# LED_Module.net
KiCad netlist of a schematic drawn in Altium Designer
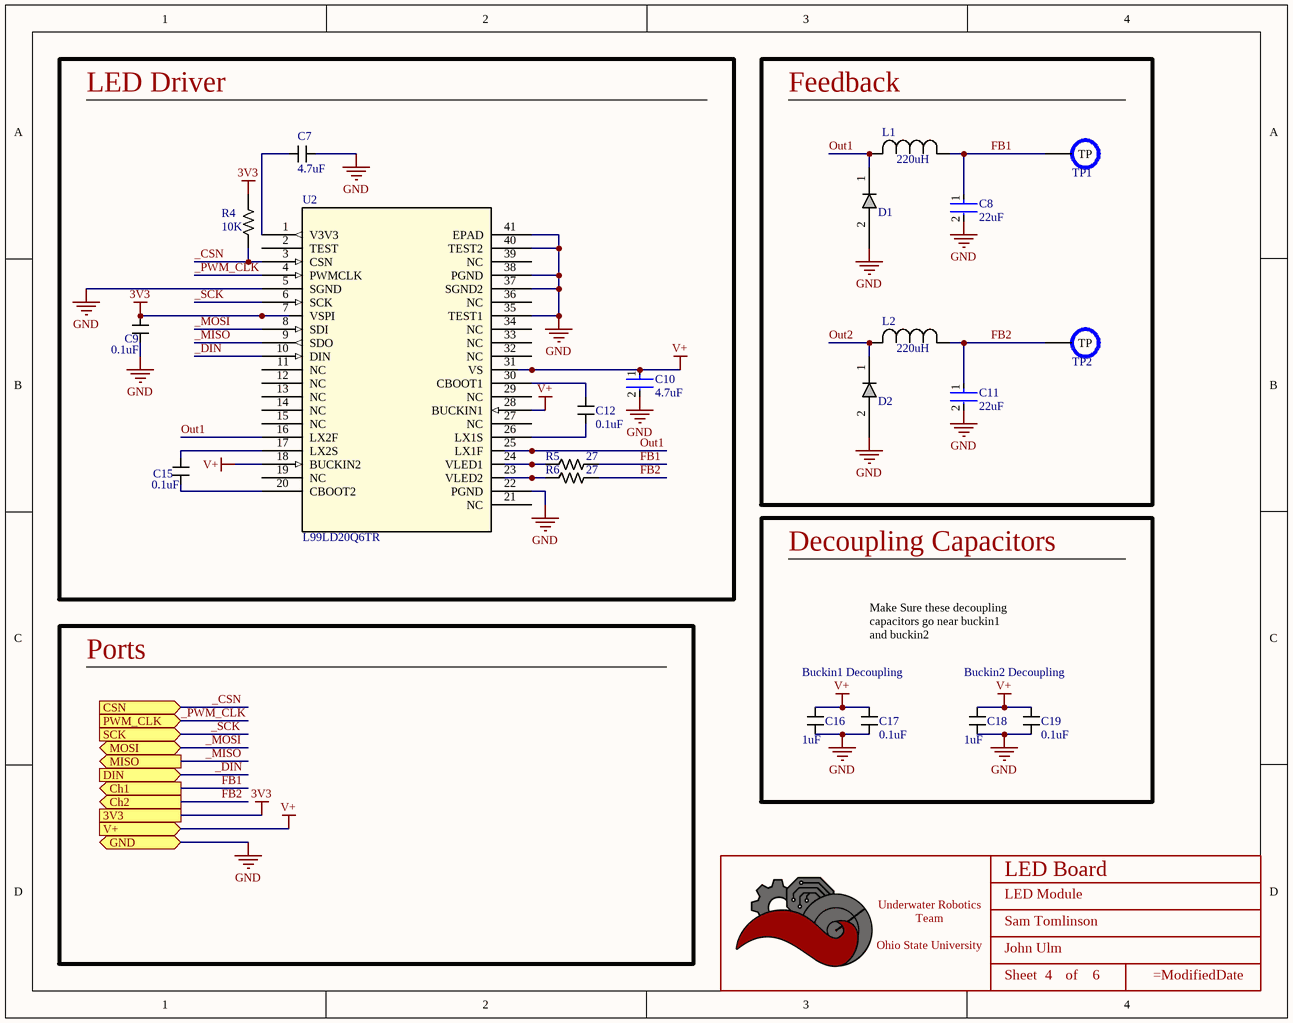
[diagram p0: LED_Module.SchDoc]

(export (version "E")
  (design (tool "Eeschema 10.0.6"))
  (components
    (comp (ref "*")
      (value "Title_Block")
      (footprint "LOGO")
      (description "UWRT Schematic Title Block Template\r\n\r\nCreated June 2021, Dylan Trainor")
      (libsource (lib "UWRT") (part "Title_Block"))
    )
    (comp (ref "C7")
      (value "4.7uF")
      (footprint "CAPACITOR_0603")
      (description "Cap 4.7uF 6.3V +/-10%\r\nCeramic 0603")
      (fields
        (field (name "TOLERANCE") "+/- 10%")
        (field (name "VOLTAGE") "6.3V")
        (field (name "MADE BY") "Robert Pafford")
      )
      (libsource (lib "Capacitors") (part "CAPACITOR_4.7uF_0603"))
    )
    (comp (ref "C8")
      (value "22uF")
      (footprint "FP-C2012-125-0_2-MFG")
      (description "Multilayer Ceramic Capacitors 22μF ±20% 35V X5R SMD 0805")
      (fields (field (name "TOLERANCE") "20%"))
      (libsource (lib "Altium Content Vault") (part "b4654b650e69147ec39a6b967a45e02"))
    )
    (comp (ref "C9")
      (value "0.1uF")
      (footprint "CAPACITOR_0603")
      (description "Cap 100nF 6.3V +/-10%\r\nCeramic 0603")
      (fields
        (field (name "TOLERANCE") "+/- 10%")
        (field (name "VOLTAGE") "6.3V")
        (field (name "MADE BY") "Flip B")
      )
      (libsource (lib "Capacitors") (part "CAPACITOR_0.1uF_0603_1"))
    )
    (comp (ref "C10")
      (value "4.7uF")
      (footprint "CAPACITOR_0603")
      (description "Chip Multilayer Ceramic Capacitors for General Purpose, 0603, 4.7uF, X5R, 15%, 20%, 35V")
      (fields (field (name "TOLERANCE") "20%"))
      (libsource (lib "Capacitors") (part "CAP CERM 4.7UF 20% 35V"))
    )
    (comp (ref "C11")
      (value "22uF")
      (footprint "FP-C2012-125-0_2-MFG")
      (description "Multilayer Ceramic Capacitors 22μF ±20% 35V X5R SMD 0805")
      (fields (field (name "TOLERANCE") "20%"))
      (libsource (lib "Altium Content Vault") (part "b4654b650e69147ec39a6b967a45e02"))
    )
    (comp (ref "C12")
      (value "0.1uF")
      (footprint "CAPACITOR_0603")
      (description "Cap 100nF 25V +/-10%\r\nCeramic 0603")
      (fields
        (field (name "TOLERANCE") "+/- 10%")
        (field (name "VOLTAGE") "6.3V")
        (field (name "MADE BY") "Flip B")
      )
      (libsource (lib "Capacitors") (part "CAPACITOR_0.1uF_0603_25V"))
    )
    (comp (ref "C15")
      (value "0.1uF")
      (footprint "CAPACITOR_0603")
      (description "Cap 100nF 25V +/-10%\r\nCeramic 0603")
      (fields
        (field (name "TOLERANCE") "+/- 10%")
        (field (name "VOLTAGE") "6.3V")
        (field (name "MADE BY") "Flip B")
      )
      (libsource (lib "Capacitors") (part "CAPACITOR_0.1uF_0603_25V"))
    )
    (comp (ref "C16")
      (value "1uF")
      (footprint "CAPACITOR_0603")
      (description "Cap 1uF 25V +/-10%\r\nCeramic 0603")
      (fields
        (field (name "TOLERANCE") "+/- 10%")
        (field (name "VOLTAGE") "16V")
        (field (name "MADE BY") "Flip B")
      )
      (libsource (lib "Capacitors") (part "CAPACITOR_1uF_0603_25V"))
    )
    (comp (ref "C17")
      (value "0.1uF")
      (footprint "CAPACITOR_0603")
      (description "Cap 100nF 25V +/-10%\r\nCeramic 0603")
      (fields
        (field (name "TOLERANCE") "+/- 10%")
        (field (name "VOLTAGE") "6.3V")
        (field (name "MADE BY") "Flip B")
      )
      (libsource (lib "Capacitors") (part "CAPACITOR_0.1uF_0603_25V"))
    )
    (comp (ref "C18")
      (value "1uF")
      (footprint "CAPACITOR_0603")
      (description "Cap 1uF 25V +/-10%\r\nCeramic 0603")
      (fields
        (field (name "TOLERANCE") "+/- 10%")
        (field (name "VOLTAGE") "16V")
        (field (name "MADE BY") "Flip B")
      )
      (libsource (lib "Capacitors") (part "CAPACITOR_1uF_0603_25V"))
    )
    (comp (ref "C19")
      (value "0.1uF")
      (footprint "CAPACITOR_0603")
      (description "Cap 100nF 25V +/-10%\r\nCeramic 0603")
      (fields
        (field (name "TOLERANCE") "+/- 10%")
        (field (name "VOLTAGE") "6.3V")
        (field (name "MADE BY") "Flip B")
      )
      (libsource (lib "Capacitors") (part "CAPACITOR_0.1uF_0603_25V"))
    )
    (comp (ref "D1")
      (value "CCS15S40,L3F")
      (footprint "SOD-963   CST2C_TOS")
      (description "DIODE SCHOTTKY 40V 1.5A CST2C")
      (fields (field (name "COPYRIGHT") "Copyright (C) 2023 Ultra Librarian. All rights reserved."))
      (libsource (lib "Diodes") (part "SCHOTTKY_40V_1.5A"))
    )
    (comp (ref "D2")
      (value "CCS15S40,L3F")
      (footprint "SOD-963   CST2C_TOS")
      (description "DIODE SCHOTTKY 40V 1.5A CST2C")
      (fields (field (name "COPYRIGHT") "Copyright (C) 2023 Ultra Librarian. All rights reserved."))
      (libsource (lib "Diodes") (part "SCHOTTKY_40V_1.5A"))
    )
    (comp (ref "L1")
      (value "SRR1280-221K")
      (footprint "IND_BOURNS_SRR1280")
      (description "220 µH Shielded Drum Core, Wirewound Inductor 1.6 A 400mOhm Max Nonstandard")
      (fields (field (name "COPYRIGHT") "Copyright (C) 2023 Ultra Librarian. All rights reserved."))
      (libsource (lib "Inductors") (part "INDUCTOR_SRR1280-221K"))
    )
    (comp (ref "L2")
      (value "SRR1280-221K")
      (footprint "IND_BOURNS_SRR1280")
      (description "220 µH Shielded Drum Core, Wirewound Inductor 1.6 A 400mOhm Max Nonstandard")
      (fields (field (name "COPYRIGHT") "Copyright (C) 2023 Ultra Librarian. All rights reserved."))
      (libsource (lib "Inductors") (part "INDUCTOR_SRR1280-221K"))
    )
    (comp (ref "R4")
      (value "10k Ohm 1% 1/16W")
      (footprint "RESISTOR_0402")
      (description "RES 10k OHM 1% 1/16W 0402")
      (fields
        (field (name "TOLERANCE") "+/- 1%")
        (field (name "VALUE  (OHMS)") "10K")
        (field (name "MADE BY") "Robert Pafford")
      )
      (libsource (lib "Resistors") (part "RESISTOR_10K_0402"))
    )
    (comp (ref "R5")
      (value "27 Ohm 5% 1/8W")
      (footprint "RESISTOR_0603")
      (description "RES 27 OHM 5% 1/8W 0603")
      (fields
        (field (name "TOLERANCE") "+/- 5%")
        (field (name "VALUE  (OHMS)") "27")
        (field (name "MADE BY") "Robert Pafford")
      )
      (libsource (lib "Resistors") (part "RESISTOR_27_0603"))
    )
    (comp (ref "R6")
      (value "27 Ohm 5% 1/8W")
      (footprint "RESISTOR_0603")
      (description "RES 27 OHM 5% 1/8W 0603")
      (fields
        (field (name "TOLERANCE") "+/- 5%")
        (field (name "VALUE  (OHMS)") "27")
        (field (name "MADE BY") "Robert Pafford")
      )
      (libsource (lib "Resistors") (part "RESISTOR_27_0603"))
    )
    (comp (ref "TP1")
      (value "PCB Test Point")
      (footprint "TESTPOINT_1.2MM")
      (fields (field (name "MADE BY") "Robert Pafford"))
      (libsource (lib "Connectors") (part "TESTPOINT"))
    )
    (comp (ref "TP2")
      (value "PCB Test Point")
      (footprint "TESTPOINT_1.2MM")
      (fields (field (name "MADE BY") "Robert Pafford"))
      (libsource (lib "Connectors") (part "TESTPOINT"))
    )
    (comp (ref "U2")
      (value "L99LD20Q6TR")
      (footprint "L99LD20Q6TR")
      (description "IC LED DRVR RGLTR PWM 1.5A 40QFN")
      (fields (field (name "COPYRIGHT") "Copyright (C) 2023 Ultra Librarian. All rights reserved."))
      (libsource (lib "Integrated Circuits") (part "L99LD20Q6TR"))
    )
  )
  (nets
    (net (code "1") (name "/FB1") (class "Default")
      (node (ref "C8") (pin "1") (pinfunction "1_1") (pintype "passive"))
      (node (ref "L1") (pin "1") (pinfunction "1_1") (pintype "passive"))
      (node (ref "R5") (pin "1") (pinfunction "1_1") (pintype "passive"))
      (node (ref "TP1") (pin "TP") (pinfunction "TP_TP") (pintype "passive"))
    )
    (net (code "2") (name "/FB2") (class "Default")
      (node (ref "C11") (pin "1") (pinfunction "1_1") (pintype "passive"))
      (node (ref "L2") (pin "1") (pinfunction "1_1") (pintype "passive"))
      (node (ref "R6") (pin "1") (pinfunction "1_1") (pintype "passive"))
      (node (ref "TP2") (pin "TP") (pinfunction "TP_TP") (pintype "passive"))
    )
    (net (code "3") (name "/Out1") (class "Default")
      (node (ref "D1") (pin "1") (pinfunction "1_1") (pintype "passive"))
      (node (ref "L1") (pin "2") (pinfunction "2_2") (pintype "passive"))
      (node (ref "U2") (pin "16") (pinfunction "LX2F_16") (pintype "passive"))
      (node (ref "U2") (pin "25") (pinfunction "LX1F_25") (pintype "passive"))
    )
    (net (code "4") (name "/Out2") (class "Default")
      (node (ref "D2") (pin "1") (pinfunction "1_1") (pintype "passive"))
      (node (ref "L2") (pin "2") (pinfunction "2_2") (pintype "passive"))
    )
    (net (code "5") (name "/_CSN") (class "Default")
      (node (ref "R4") (pin "2") (pinfunction "2_2") (pintype "passive"))
      (node (ref "U2") (pin "3") (pinfunction "CSN_3") (pintype "input"))
    )
    (net (code "6") (name "/_DIN") (class "Default")
      (node (ref "U2") (pin "10") (pinfunction "DIN_10") (pintype "input"))
    )
    (net (code "7") (name "/_MISO") (class "Default")
      (node (ref "U2") (pin "9") (pinfunction "SDO_9") (pintype "output"))
    )
    (net (code "8") (name "/_MOSI") (class "Default")
      (node (ref "U2") (pin "8") (pinfunction "SDI_8") (pintype "input"))
    )
    (net (code "9") (name "/_PWM_CLK") (class "Default")
      (node (ref "U2") (pin "4") (pinfunction "PWMCLK_4") (pintype "input"))
    )
    (net (code "10") (name "/_SCK") (class "Default")
      (node (ref "U2") (pin "6") (pinfunction "SCK_6") (pintype "input"))
    )
    (net (code "11") (name "3V3") (class "Default")
      (node (ref "C9") (pin "1") (pinfunction "1_1") (pintype "passive"))
      (node (ref "R4") (pin "1") (pinfunction "1_1") (pintype "passive"))
      (node (ref "U2") (pin "7") (pinfunction "VSPI_7") (pintype "passive"))
    )
    (net (code "12") (name "GND") (class "Default")
      (node (ref "C10") (pin "2") (pinfunction "2_2") (pintype "passive"))
      (node (ref "C11") (pin "2") (pinfunction "2_2") (pintype "passive"))
      (node (ref "C16") (pin "1") (pinfunction "1_1") (pintype "passive"))
      (node (ref "C17") (pin "2") (pinfunction "2_2") (pintype "passive"))
      (node (ref "C18") (pin "1") (pinfunction "1_1") (pintype "passive"))
      (node (ref "C19") (pin "2") (pinfunction "2_2") (pintype "passive"))
      (node (ref "C7") (pin "1") (pinfunction "1_1") (pintype "passive"))
      (node (ref "C8") (pin "2") (pinfunction "2_2") (pintype "passive"))
      (node (ref "C9") (pin "2") (pinfunction "2_2") (pintype "passive"))
      (node (ref "D1") (pin "2") (pinfunction "2_2") (pintype "passive"))
      (node (ref "D2") (pin "2") (pinfunction "2_2") (pintype "passive"))
      (node (ref "U2") (pin "22") (pinfunction "PGND_22") (pintype "power_in"))
      (node (ref "U2") (pin "35") (pinfunction "TEST1_35") (pintype "passive"))
      (node (ref "U2") (pin "37") (pinfunction "SGND2_37") (pintype "power_in"))
      (node (ref "U2") (pin "38") (pinfunction "PGND_38") (pintype "power_in"))
      (node (ref "U2") (pin "40") (pinfunction "TEST2_40") (pintype "passive"))
      (node (ref "U2") (pin "41") (pinfunction "EPAD_41") (pintype "power_in"))
      (node (ref "U2") (pin "5") (pinfunction "SGND_5") (pintype "power_in"))
    )
    (net (code "13") (name "Net-(U2-CBOOT1)") (class "Default")
      (node (ref "C12") (pin "1") (pinfunction "1_1") (pintype "passive"))
      (node (ref "U2") (pin "30") (pinfunction "CBOOT1_30") (pintype "passive"))
    )
    (net (code "14") (name "Net-(U2-CBOOT2)") (class "Default")
      (node (ref "C15") (pin "2") (pinfunction "2_2") (pintype "passive"))
      (node (ref "U2") (pin "20") (pinfunction "CBOOT2_20") (pintype "passive"))
    )
    (net (code "15") (name "Net-(U2-LX1S)") (class "Default")
      (node (ref "C12") (pin "2") (pinfunction "2_2") (pintype "passive"))
      (node (ref "U2") (pin "26") (pinfunction "LX1S_26") (pintype "passive"))
    )
    (net (code "16") (name "Net-(U2-LX2S)") (class "Default")
      (node (ref "C15") (pin "1") (pinfunction "1_1") (pintype "passive"))
      (node (ref "U2") (pin "17") (pinfunction "LX2S_17") (pintype "passive"))
    )
    (net (code "17") (name "Net-(U2-V3V3)") (class "Default")
      (node (ref "C7") (pin "2") (pinfunction "2_2") (pintype "passive"))
      (node (ref "U2") (pin "1") (pinfunction "V3V3_1") (pintype "output"))
    )
    (net (code "18") (name "Net-(U2-VLED1)") (class "Default")
      (node (ref "R5") (pin "2") (pinfunction "2_2") (pintype "passive"))
      (node (ref "U2") (pin "24") (pinfunction "VLED1_24") (pintype "passive"))
    )
    (net (code "19") (name "Net-(U2-VLED2)") (class "Default")
      (node (ref "R6") (pin "2") (pinfunction "2_2") (pintype "passive"))
      (node (ref "U2") (pin "23") (pinfunction "VLED2_23") (pintype "passive"))
    )
    (net (code "20") (name "V+") (class "Default")
      (node (ref "C10") (pin "1") (pinfunction "1_1") (pintype "passive"))
      (node (ref "C16") (pin "2") (pinfunction "2_2") (pintype "passive"))
      (node (ref "C17") (pin "1") (pinfunction "1_1") (pintype "passive"))
      (node (ref "C18") (pin "2") (pinfunction "2_2") (pintype "passive"))
      (node (ref "C19") (pin "1") (pinfunction "1_1") (pintype "passive"))
      (node (ref "U2") (pin "18") (pinfunction "BUCKIN2_18") (pintype "input"))
      (node (ref "U2") (pin "28") (pinfunction "BUCKIN1_28") (pintype "input"))
      (node (ref "U2") (pin "31") (pinfunction "VS_31") (pintype "passive"))
    )
    (net (code "21") (name "unconnected-(U2-NC-Pad11)") (class "Default")
      (node (ref "U2") (pin "11") (pinfunction "NC_11") (pintype "passive"))
    )
    (net (code "22") (name "unconnected-(U2-NC-Pad12)") (class "Default")
      (node (ref "U2") (pin "12") (pinfunction "NC_12") (pintype "passive"))
    )
    (net (code "23") (name "unconnected-(U2-NC-Pad13)") (class "Default")
      (node (ref "U2") (pin "13") (pinfunction "NC_13") (pintype "passive"))
    )
    (net (code "24") (name "unconnected-(U2-NC-Pad14)") (class "Default")
      (node (ref "U2") (pin "14") (pinfunction "NC_14") (pintype "passive"))
    )
    (net (code "25") (name "unconnected-(U2-NC-Pad15)") (class "Default")
      (node (ref "U2") (pin "15") (pinfunction "NC_15") (pintype "passive"))
    )
    (net (code "26") (name "unconnected-(U2-NC-Pad19)") (class "Default")
      (node (ref "U2") (pin "19") (pinfunction "NC_19") (pintype "passive"))
    )
    (net (code "27") (name "unconnected-(U2-NC-Pad21)") (class "Default")
      (node (ref "U2") (pin "21") (pinfunction "NC_21") (pintype "passive"))
    )
    (net (code "28") (name "unconnected-(U2-NC-Pad27)") (class "Default")
      (node (ref "U2") (pin "27") (pinfunction "NC_27") (pintype "passive"))
    )
    (net (code "29") (name "unconnected-(U2-NC-Pad29)") (class "Default")
      (node (ref "U2") (pin "29") (pinfunction "NC_29") (pintype "passive"))
    )
    (net (code "30") (name "unconnected-(U2-NC-Pad32)") (class "Default")
      (node (ref "U2") (pin "32") (pinfunction "NC_32") (pintype "passive"))
    )
    (net (code "31") (name "unconnected-(U2-NC-Pad33)") (class "Default")
      (node (ref "U2") (pin "33") (pinfunction "NC_33") (pintype "passive"))
    )
    (net (code "32") (name "unconnected-(U2-NC-Pad34)") (class "Default")
      (node (ref "U2") (pin "34") (pinfunction "NC_34") (pintype "passive"))
    )
    (net (code "33") (name "unconnected-(U2-NC-Pad36)") (class "Default")
      (node (ref "U2") (pin "36") (pinfunction "NC_36") (pintype "passive"))
    )
    (net (code "34") (name "unconnected-(U2-NC-Pad39)") (class "Default")
      (node (ref "U2") (pin "39") (pinfunction "NC_39") (pintype "passive"))
    )
    (net (code "35") (name "unconnected-(U2-TEST-Pad2)") (class "Default")
      (node (ref "U2") (pin "2") (pinfunction "TEST_2") (pintype "passive"))
    )
  )
)
